# STlink_V3E_Module.net
KiCad netlist of a schematic drawn in Altium Designer
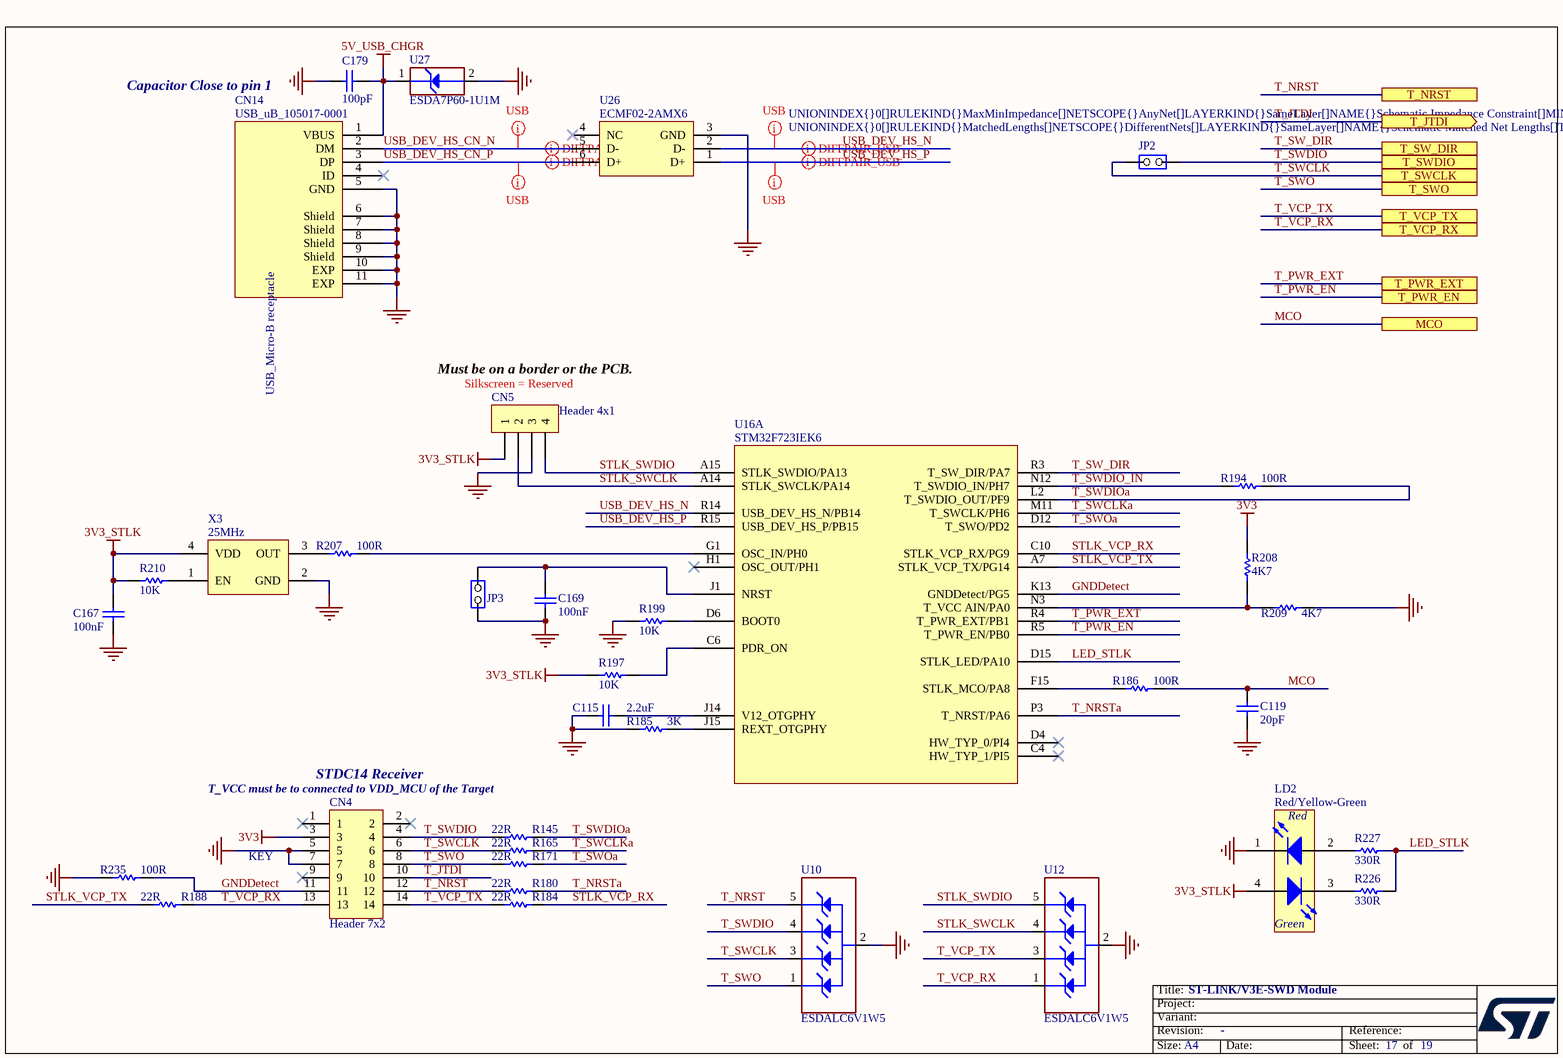
[diagram p0: STlink_V3E_Module.SchDoc]

(export (version "E")
  (design (tool "Eeschema 10.0.6"))
  (components
    (comp (ref "C115")
      (value "2.2uF")
      (footprint "C0603")
      (description "Capacitor, MLCC, 2.2uF, 10V, X5R, 10%, 0603, T=0,8mm")
      (fields
        (field (name "INTERNAL_PART_NUMBER") "MCD-00012")
        (field (name "MANUFACTURER_PART_NUMBER") "CC0603KRX5R6BB225")
        (field (name "PROVIDED_BY") "Subcon")
      )
      (libsource (lib "MCD_PARTS_database") (part "Capacitor"))
    )
    (comp (ref "C119")
      (value "20pF")
      (footprint "C0402")
      (description "Capacitor, MLCC, 20pF, 50V, NPO, 5%, 0402, T=0,5mm")
      (fields
        (field (name "INTERNAL_PART_NUMBER") "MCD-00016")
        (field (name "MANUFACTURER_PART_NUMBER") "CC0402JRNPO9BN200")
        (field (name "PROVIDED_BY") "Subcon")
      )
      (libsource (lib "MCD_PARTS_database") (part "Capacitor"))
    )
    (comp (ref "C167")
      (value "100nF")
      (footprint "C0402")
      (description "Capacitor, MLCC, 100nF, 16V, X7R, +/-10%, 0402, T=0.5mm")
      (fields
        (field (name "INTERNAL_PART_NUMBER") "MCD-00006")
        (field (name "MANUFACTURER_PART_NUMBER") "CC0402KRX7R7BB104")
      )
      (libsource (lib "MCD_PARTS_database") (part "Capacitor"))
    )
    (comp (ref "C169")
      (value "100nF")
      (footprint "C0402")
      (description "Capacitor, MLCC, 100nF, 16V, X7R, +/-10%, 0402, T=0.5mm")
      (fields
        (field (name "INTERNAL_PART_NUMBER") "MCD-00006")
        (field (name "MANUFACTURER_PART_NUMBER") "CC0402KRX7R7BB104")
      )
      (libsource (lib "MCD_PARTS_database") (part "Capacitor"))
    )
    (comp (ref "C179")
      (value "100pF")
      (footprint "C0402")
      (description "Capacitor, MLCC, 100pF, 50V, NPO, 5%, 0402, T=0,5mm")
      (fields
        (field (name "INTERNAL_PART_NUMBER") "MCD-00205")
        (field (name "MANUFACTURER_PART_NUMBER") "CC0402JRNPO9BN101")
        (field (name "PROVIDED_BY") "Subcon")
      )
      (libsource (lib "MCD_PARTS_database") (part "Capacitor"))
    )
    (comp (ref "CN4")
      (value "Header 7x2")
      (footprint "CON_STDC14_Receiver_MEDIUM")
      (description "Header, 7x2, 1.27mm, VR, SMD, T=5.97mm")
      (fields
        (field (name "INTERNAL_PART_NUMBER") "MCD-00592")
        (field (name "MANUFACTURER_PART_NUMBER") "FTSH-107-01-L-DV-K")
      )
      (libsource (lib "MCD_PARTS_database") (part "Header 7x2"))
    )
    (comp (ref "CN5")
      (value "Header 4x1")
      (footprint "CON_SAMTEC_TSW-104-07-G-S")
      (description "Header, 4x1, 2,54mm, VR, TH, Height 5.84mm/2.54mm")
      (fields
        (field (name "INTERNAL_PART_NUMBER") "MCD-00029")
        (field (name "MANUFACTURER_PART_NUMBER") "TSW-104-07-G-S")
        (field (name "PROVIDED_BY") "Subcon")
      )
      (libsource (lib "MCD_PARTS_database") (part "Header 4x1"))
    )
    (comp (ref "CN14")
      (value "USB_uB_105017-0001")
      (footprint "CON_USBMICROB_MOLEX_105017-0001_H2P90")
      (description "USB-MICRO-B, 0.65mm, RA, SMT, Bottom Mount,")
      (fields
        (field (name "INTERNAL_PART_NUMBER") "MCD-00028")
        (field (name "MANUFACTURER_PART_NUMBER") "1050170001")
        (field (name "PROVIDED_BY") "Subcon")
      )
      (libsource (lib "MCD_PARTS_database") (part "USB_uB_105017.0001"))
    )
    (comp (ref "JP2")
      (value "Jumper Header 2x1")
      (footprint "CON_SAMTEC_TSW-102-07-G-S")
      (description "Header, 2x1, 2,54mm, VR, TH, Height 5.84mm/2.54mm")
      (fields
        (field (name "INTERNAL_PART_NUMBER") "MCD-00045")
        (field (name "MANUFACTURER_PART_NUMBER") "TSW-102-07-G-S")
        (field (name "PROVIDED_BY") "Subcon")
      )
      (libsource (lib "MCD_PARTS_database") (part "Jumper Header 2x1"))
    )
    (comp (ref "JP3")
      (value "Jumper Header 2x1")
      (footprint "CON_SAMTEC_TSW-102-07-G-S")
      (description "Header, 2x1, 2,54mm, VR, TH, Height 5.84mm/2.54mm")
      (fields
        (field (name "INTERNAL_PART_NUMBER") "MCD-00045")
        (field (name "MANUFACTURER_PART_NUMBER") "TSW-102-07-G-S")
        (field (name "PROVIDED_BY") "Subcon")
      )
      (libsource (lib "MCD_PARTS_database") (part "Jumper Header 2x1"))
    )
    (comp (ref "LD2")
      (value "Red/Yellow-Green")
      (footprint "LED_BI-GR_HSMF-A201-A00J1")
      (description "LED Bicolor, Red/Yellow-Green , 2V, 20mA, 4-PLCC")
      (fields
        (field (name "INTERNAL_PART_NUMBER") "MCD-02402")
        (field (name "MANUFACTURER_PART_NUMBER") "67-22SURSYGC/S530-A2/TR8")
      )
      (libsource (lib "MCD_PARTS_database") (part "LD_BICOLOR_CMS"))
    )
    (comp (ref "R145")
      (value "22R")
      (footprint "R0402")
      (description "Resistor,22R,0402,1%,1/16W")
      (fields
        (field (name "INTERNAL_PART_NUMBER") "MCD-00189")
        (field (name "MANUFACTURER_PART_NUMBER") "RC0402FR-0722RL")
        (field (name "PROVIDED_BY") "Subcon")
      )
      (libsource (lib "MCD_PARTS_database") (part "Resistor"))
    )
    (comp (ref "R165")
      (value "22R")
      (footprint "R0402")
      (description "Resistor,22R,0402,1%,1/16W")
      (fields
        (field (name "INTERNAL_PART_NUMBER") "MCD-00189")
        (field (name "MANUFACTURER_PART_NUMBER") "RC0402FR-0722RL")
        (field (name "PROVIDED_BY") "Subcon")
      )
      (libsource (lib "MCD_PARTS_database") (part "Resistor"))
    )
    (comp (ref "R171")
      (value "22R")
      (footprint "R0402")
      (description "Resistor,22R,0402,1%,1/16W")
      (fields
        (field (name "INTERNAL_PART_NUMBER") "MCD-00189")
        (field (name "MANUFACTURER_PART_NUMBER") "RC0402FR-0722RL")
        (field (name "PROVIDED_BY") "Subcon")
      )
      (libsource (lib "MCD_PARTS_database") (part "Resistor"))
    )
    (comp (ref "R180")
      (value "22R")
      (footprint "R0402")
      (description "Resistor,22R,0402,1%,1/16W")
      (fields
        (field (name "INTERNAL_PART_NUMBER") "MCD-00189")
        (field (name "MANUFACTURER_PART_NUMBER") "RC0402FR-0722RL")
        (field (name "PROVIDED_BY") "Subcon")
      )
      (libsource (lib "MCD_PARTS_database") (part "Resistor"))
    )
    (comp (ref "R184")
      (value "22R")
      (footprint "R0402")
      (description "Resistor,22R,0402,1%,1/16W")
      (fields
        (field (name "INTERNAL_PART_NUMBER") "MCD-00189")
        (field (name "MANUFACTURER_PART_NUMBER") "RC0402FR-0722RL")
        (field (name "PROVIDED_BY") "Subcon")
      )
      (libsource (lib "MCD_PARTS_database") (part "Resistor"))
    )
    (comp (ref "R185")
      (value "3K")
      (footprint "R0402")
      (description "Resistor,3K,0402,1%,1/16W")
      (fields
        (field (name "INTERNAL_PART_NUMBER") "MCD-00185")
        (field (name "MANUFACTURER_PART_NUMBER") "RC0402FR-073KL")
        (field (name "PROVIDED_BY") "Subcon")
      )
      (libsource (lib "MCD_PARTS_database") (part "Resistor"))
    )
    (comp (ref "R186")
      (value "100R")
      (footprint "R0402")
      (description "Resistor, 100R, 0402, +/- 1%, 1/16W")
      (fields
        (field (name "INTERNAL_PART_NUMBER") "MCD-00067")
        (field (name "MANUFACTURER_PART_NUMBER") "RC0402FR-07100RL")
      )
      (libsource (lib "MCD_PARTS_database") (part "Resistor"))
    )
    (comp (ref "R188")
      (value "22R")
      (footprint "R0402")
      (description "Resistor,22R,0402,1%,1/16W")
      (fields
        (field (name "INTERNAL_PART_NUMBER") "MCD-00189")
        (field (name "MANUFACTURER_PART_NUMBER") "RC0402FR-0722RL")
        (field (name "PROVIDED_BY") "Subcon")
      )
      (libsource (lib "MCD_PARTS_database") (part "Resistor"))
    )
    (comp (ref "R194")
      (value "100R")
      (footprint "R0402")
      (description "Resistor, 100R, 0402, +/- 1%, 1/16W")
      (fields
        (field (name "INTERNAL_PART_NUMBER") "MCD-00067")
        (field (name "MANUFACTURER_PART_NUMBER") "RC0402FR-07100RL")
      )
      (libsource (lib "MCD_PARTS_database") (part "Resistor"))
    )
    (comp (ref "R197")
      (value "10K")
      (footprint "R0402")
      (description "Resistor,10K,0402,1%,1/16W")
      (fields
        (field (name "INTERNAL_PART_NUMBER") "MCD-00053")
        (field (name "MANUFACTURER_PART_NUMBER") "RC0402FR-0710KL")
        (field (name "PROVIDED_BY") "subcon")
      )
      (libsource (lib "MCD_PARTS_database") (part "Resistor"))
    )
    (comp (ref "R199")
      (value "10K")
      (footprint "R0402")
      (description "Resistor,10K,0402,1%,1/16W")
      (fields
        (field (name "INTERNAL_PART_NUMBER") "MCD-00053")
        (field (name "MANUFACTURER_PART_NUMBER") "RC0402FR-0710KL")
        (field (name "PROVIDED_BY") "subcon")
      )
      (libsource (lib "MCD_PARTS_database") (part "Resistor"))
    )
    (comp (ref "R207")
      (value "100R")
      (footprint "R0402")
      (description "Resistor, 100R, 0402, +/- 1%, 1/16W")
      (fields
        (field (name "INTERNAL_PART_NUMBER") "MCD-00067")
        (field (name "MANUFACTURER_PART_NUMBER") "RC0402FR-07100RL")
      )
      (libsource (lib "MCD_PARTS_database") (part "Resistor"))
    )
    (comp (ref "R208")
      (value "4K7")
      (footprint "R0402")
      (description "Resistor,4K7,0402,1%,1/16W")
      (fields
        (field (name "INTERNAL_PART_NUMBER") "MCD-00065")
        (field (name "MANUFACTURER_PART_NUMBER") "RC0402FR-074K7L")
        (field (name "PROVIDED_BY") "Subcon")
      )
      (libsource (lib "MCD_PARTS_database") (part "Resistor"))
    )
    (comp (ref "R209")
      (value "4K7")
      (footprint "R0402")
      (description "Resistor,4K7,0402,1%,1/16W")
      (fields
        (field (name "INTERNAL_PART_NUMBER") "MCD-00065")
        (field (name "MANUFACTURER_PART_NUMBER") "RC0402FR-074K7L")
        (field (name "PROVIDED_BY") "Subcon")
      )
      (libsource (lib "MCD_PARTS_database") (part "Resistor"))
    )
    (comp (ref "R210")
      (value "10K")
      (footprint "R0402")
      (description "Resistor,10K,0402,1%,1/16W")
      (fields
        (field (name "INTERNAL_PART_NUMBER") "MCD-00053")
        (field (name "MANUFACTURER_PART_NUMBER") "RC0402FR-0710KL")
        (field (name "PROVIDED_BY") "subcon")
      )
      (libsource (lib "MCD_PARTS_database") (part "Resistor"))
    )
    (comp (ref "R226")
      (value "330R")
      (footprint "R0603")
      (description "Resistor,330R,0603,1%,1/10W")
      (fields
        (field (name "INTERNAL_PART_NUMBER") "MCD-00197")
        (field (name "MANUFACTURER_PART_NUMBER") "RC0603FR-07330RL")
        (field (name "PROVIDED_BY") "Subcon")
      )
      (libsource (lib "MCD_PARTS_database") (part "Resistor"))
    )
    (comp (ref "R227")
      (value "330R")
      (footprint "R0603")
      (description "Resistor,330R,0603,1%,1/10W")
      (fields
        (field (name "INTERNAL_PART_NUMBER") "MCD-00197")
        (field (name "MANUFACTURER_PART_NUMBER") "RC0603FR-07330RL")
        (field (name "PROVIDED_BY") "Subcon")
      )
      (libsource (lib "MCD_PARTS_database") (part "Resistor"))
    )
    (comp (ref "R235")
      (value "100R")
      (footprint "R0402")
      (description "Resistor, 100R, 0402, +/- 1%, 1/16W")
      (fields
        (field (name "INTERNAL_PART_NUMBER") "MCD-00067")
        (field (name "MANUFACTURER_PART_NUMBER") "RC0402FR-07100RL")
      )
      (libsource (lib "MCD_PARTS_database") (part "Resistor"))
    )
    (comp (ref "U10")
      (value "ESDALC6V1W5")
      (footprint "ESD_SOT323-5L")
      (description "Dual Transil array for ESD protection")
      (fields
        (field (name "INTERNAL_PART_NUMBER") "MCD-00136")
        (field (name "MANUFACTURER") "STMICROELECTRONICS")
        (field (name "PROVIDED_BY") "Subcon")
      )
      (libsource (lib "MCD_PARTS_database") (part "ESDALC6V1W5"))
    )
    (comp (ref "U12")
      (value "ESDALC6V1W5")
      (footprint "ESD_SOT323-5L")
      (description "Dual Transil array for ESD protection")
      (fields
        (field (name "INTERNAL_PART_NUMBER") "MCD-00136")
        (field (name "MANUFACTURER") "STMICROELECTRONICS")
        (field (name "PROVIDED_BY") "Subcon")
      )
      (libsource (lib "MCD_PARTS_database") (part "ESDALC6V1W5"))
    )
    (comp (ref "U16")
      (value "STM32F723IEK6")
      (footprint "ICC_UFBGA201_176+25_10X10_P065")
      (description "STM32F723IEK  (STM32F7) BGA176")
      (fields
        (field (name "INTERNAL_PART_NUMBER") "MCD-00596")
        (field (name "MANUFACTURER") "STMICROELECTRONICS")
        (field (name "PROVIDED_BY") "SUBCO with ST control")
      )
      (libsource (lib "MCD_PARTS_database") (part "ST-LINKV3E_SWD"))
    )
    (comp (ref "U26")
      (value "ECMF02-2AMX6")
      (footprint "ESD_QFN-6L_1P7X1P5_P050")
      (description "Common mode filter with ESD protection for USB 2.0 interface")
      (fields
        (field (name "INTERNAL_PART_NUMBER") "MCD-00649")
        (field (name "MANUFACTURER") "STMICROELECTRONICS")
        (field (name "PROVIDED_BY") "Subcon")
      )
      (libsource (lib "MCD_PARTS_database") (part "ECMF02-2AMX6"))
    )
    (comp (ref "U27")
      (value "ESDA7P60-1U1M")
      (footprint "ESD_QFN2_1P6X1_P125")
      (description "High power transient voltage suppressor, 7V breakdown")
      (fields
        (field (name "INTERNAL_PART_NUMBER") "MCD-00251")
        (field (name "MANUFACTURER") "STMICROELECTRONICS")
        (field (name "PROVIDED_BY") "Subcon")
      )
      (libsource (lib "MCD_PARTS_database") (part "ESDA7P60-1U1M"))
    )
    (comp (ref "X3")
      (value "25MHz")
      (footprint "OSC_NDK_NZ2520SB_4P")
      (description "Oscillator 25.00Mhz, -+50PPM, 3.3V, Temp -55 to +125°C")
      (fields
        (field (name "INTERNAL_PART_NUMBER") "MCD-00597")
        (field (name "MANUFACTURER_PART_NUMBER") "NZ2520SH-25MHZ-END4869C")
        (field (name "PROVIDED_BY") "STM")
      )
      (libsource (lib "MCD_PARTS_database") (part "Oscillator_4pins"))
    )
  )
  (nets
    (net (code "1") (name "/GNDDetect") (class "Default")
      (node (ref "CN4") (pin "11") (pinfunction "11_11") (pintype "passive"))
      (node (ref "R235") (pin "2") (pinfunction "2_2") (pintype "passive"))
      (node (ref "U16") (pin "K13") (pinfunction "GNDDetect/PG5_K13") (pintype "passive"))
    )
    (net (code "2") (name "/LED_STLK") (class "Default")
      (node (ref "R226") (pin "2") (pinfunction "2_2") (pintype "passive"))
      (node (ref "R227") (pin "2") (pinfunction "2_2") (pintype "passive"))
      (node (ref "U16") (pin "D15") (pinfunction "STLK_LED/PA10_D15") (pintype "passive"))
    )
    (net (code "3") (name "/MCO") (class "Default")
      (node (ref "C119") (pin "2") (pinfunction "2_2") (pintype "passive"))
      (node (ref "R186") (pin "2") (pinfunction "2_2") (pintype "passive"))
    )
    (net (code "4") (name "/STLK_SWCLK") (class "Default")
      (node (ref "CN5") (pin "2") (pinfunction "2_2") (pintype "passive"))
      (node (ref "U12") (pin "4") (pinfunction "IO3_4") (pintype "passive"))
      (node (ref "U16") (pin "A14") (pinfunction "STLK_SWCLK/PA14_A14") (pintype "passive"))
    )
    (net (code "5") (name "/STLK_SWDIO") (class "Default")
      (node (ref "CN5") (pin "4") (pinfunction "4_4") (pintype "passive"))
      (node (ref "U12") (pin "5") (pinfunction "IO4_5") (pintype "passive"))
      (node (ref "U16") (pin "A15") (pinfunction "STLK_SWDIO/PA13_A15") (pintype "passive"))
    )
    (net (code "6") (name "/STLK_VCP_RX") (class "Default")
      (node (ref "R184") (pin "2") (pinfunction "2_2") (pintype "passive"))
      (node (ref "U16") (pin "C10") (pinfunction "STLK_VCP_RX/PG9_C10") (pintype "passive"))
    )
    (net (code "7") (name "/STLK_VCP_TX") (class "Default")
      (node (ref "R188") (pin "1") (pinfunction "1_1") (pintype "passive"))
      (node (ref "U16") (pin "A7") (pinfunction "STLK_VCP_TX/PG14_A7") (pintype "passive"))
    )
    (net (code "8") (name "/T_JTDI") (class "Default")
      (node (ref "CN4") (pin "10") (pinfunction "10_10") (pintype "passive"))
    )
    (net (code "9") (name "/T_NRST") (class "Default")
      (node (ref "CN4") (pin "12") (pinfunction "12_12") (pintype "passive"))
      (node (ref "R180") (pin "1") (pinfunction "1_1") (pintype "passive"))
      (node (ref "U10") (pin "5") (pinfunction "IO4_5") (pintype "passive"))
    )
    (net (code "10") (name "/T_NRSTa") (class "Default")
      (node (ref "R180") (pin "2") (pinfunction "2_2") (pintype "passive"))
      (node (ref "U16") (pin "P3") (pinfunction "T_NRST/PA6_P3") (pintype "passive"))
    )
    (net (code "11") (name "/T_PWR_EN") (class "Default")
      (node (ref "U16") (pin "R5") (pinfunction "T_PWR_EN/PB0_R5") (pintype "passive"))
    )
    (net (code "12") (name "/T_PWR_EXT") (class "Default")
      (node (ref "U16") (pin "R4") (pinfunction "T_PWR_EXT/PB1_R4") (pintype "passive"))
    )
    (net (code "13") (name "/T_SWCLK") (class "Default")
      (node (ref "CN4") (pin "6") (pinfunction "6_6") (pintype "passive"))
      (node (ref "JP2") (pin "1") (pinfunction "COMMON_1") (pintype "passive"))
      (node (ref "R165") (pin "1") (pinfunction "1_1") (pintype "passive"))
      (node (ref "U10") (pin "3") (pinfunction "IO2_3") (pintype "passive"))
    )
    (net (code "14") (name "/T_SWCLKa") (class "Default")
      (node (ref "R165") (pin "2") (pinfunction "2_2") (pintype "passive"))
      (node (ref "U16") (pin "M11") (pinfunction "T_SWCLK/PH6_M11") (pintype "passive"))
    )
    (net (code "15") (name "/T_SWDIO") (class "Default")
      (node (ref "CN4") (pin "4") (pinfunction "4_4") (pintype "passive"))
      (node (ref "JP2") (pin "2") (pinfunction "NO_2") (pintype "passive"))
      (node (ref "R145") (pin "1") (pinfunction "1_1") (pintype "passive"))
      (node (ref "U10") (pin "4") (pinfunction "IO3_4") (pintype "passive"))
    )
    (net (code "16") (name "/T_SWDIO_IN") (class "Default")
      (node (ref "R194") (pin "1") (pinfunction "1_1") (pintype "passive"))
      (node (ref "U16") (pin "N12") (pinfunction "T_SWDIO_IN/PH7_N12") (pintype "passive"))
    )
    (net (code "17") (name "/T_SWDIOa") (class "Default")
      (node (ref "R145") (pin "2") (pinfunction "2_2") (pintype "passive"))
      (node (ref "R194") (pin "2") (pinfunction "2_2") (pintype "passive"))
      (node (ref "U16") (pin "L2") (pinfunction "T_SWDIO_OUT/PF9_L2") (pintype "passive"))
    )
    (net (code "18") (name "/T_SWO") (class "Default")
      (node (ref "CN4") (pin "8") (pinfunction "8_8") (pintype "passive"))
      (node (ref "R171") (pin "1") (pinfunction "1_1") (pintype "passive"))
      (node (ref "U10") (pin "1") (pinfunction "IO1_1") (pintype "passive"))
    )
    (net (code "19") (name "/T_SWOa") (class "Default")
      (node (ref "R171") (pin "2") (pinfunction "2_2") (pintype "passive"))
      (node (ref "U16") (pin "D12") (pinfunction "T_SWO/PD2_D12") (pintype "passive"))
    )
    (net (code "20") (name "/T_SW_DIR") (class "Default")
      (node (ref "U16") (pin "R3") (pinfunction "T_SW_DIR/PA7_R3") (pintype "passive"))
    )
    (net (code "21") (name "/T_VCP_RX") (class "Default")
      (node (ref "CN4") (pin "13") (pinfunction "13_13") (pintype "passive"))
      (node (ref "R188") (pin "2") (pinfunction "2_2") (pintype "passive"))
      (node (ref "U12") (pin "1") (pinfunction "IO1_1") (pintype "passive"))
    )
    (net (code "22") (name "/T_VCP_TX") (class "Default")
      (node (ref "CN4") (pin "14") (pinfunction "14_14") (pintype "passive"))
      (node (ref "R184") (pin "1") (pinfunction "1_1") (pintype "passive"))
      (node (ref "U12") (pin "3") (pinfunction "IO2_3") (pintype "passive"))
    )
    (net (code "23") (name "/USB_DEV_HS_CN_N") (class "Default")
      (node (ref "CN14") (pin "2") (pinfunction "DM_2") (pintype "passive"))
      (node (ref "U26") (pin "5") (pinfunction "D-_5") (pintype "passive"))
    )
    (net (code "24") (name "/USB_DEV_HS_CN_P") (class "Default")
      (node (ref "CN14") (pin "3") (pinfunction "DP_3") (pintype "passive"))
      (node (ref "U26") (pin "6") (pinfunction "D+_6") (pintype "passive"))
    )
    (net (code "25") (name "/USB_DEV_HS_N") (class "Default")
      (node (ref "U16") (pin "R14") (pinfunction "USB_DEV_HS_N/PB14_R14") (pintype "passive"))
      (node (ref "U26") (pin "2") (pinfunction "D-_2") (pintype "passive"))
    )
    (net (code "26") (name "/USB_DEV_HS_P") (class "Default")
      (node (ref "U16") (pin "R15") (pinfunction "USB_DEV_HS_P/PB15_R15") (pintype "passive"))
      (node (ref "U26") (pin "1") (pinfunction "D+_1") (pintype "passive"))
    )
    (net (code "27") (name "3V3") (class "Default")
      (node (ref "CN4") (pin "3") (pinfunction "3_3") (pintype "passive"))
      (node (ref "R208") (pin "2") (pinfunction "2_2") (pintype "passive"))
    )
    (net (code "28") (name "3V3_STLK") (class "Default")
      (node (ref "C167") (pin "2") (pinfunction "2_2") (pintype "passive"))
      (node (ref "CN5") (pin "1") (pinfunction "1_1") (pintype "passive"))
      (node (ref "LD2") (pin "4") (pinfunction "YellowGreen_anode_4") (pintype "passive"))
      (node (ref "R197") (pin "1") (pinfunction "1_1") (pintype "passive"))
      (node (ref "R210") (pin "1") (pinfunction "1_1") (pintype "passive"))
      (node (ref "X3") (pin "4") (pinfunction "VDD_4") (pintype "passive"))
    )
    (net (code "29") (name "5V_USB_CHGR") (class "Default")
      (node (ref "C179") (pin "2") (pinfunction "2_2") (pintype "passive"))
      (node (ref "CN14") (pin "1") (pinfunction "VBUS_1") (pintype "passive"))
      (node (ref "U27") (pin "1") (pinfunction "IO1_1") (pintype "passive"))
    )
    (net (code "30") (name "GND") (class "Default")
      (node (ref "C115") (pin "1") (pinfunction "1_1") (pintype "passive"))
      (node (ref "C119") (pin "1") (pinfunction "1_1") (pintype "passive"))
      (node (ref "C167") (pin "1") (pinfunction "1_1") (pintype "passive"))
      (node (ref "C169") (pin "1") (pinfunction "1_1") (pintype "passive"))
      (node (ref "C179") (pin "1") (pinfunction "1_1") (pintype "passive"))
      (node (ref "CN14") (pin "10") (pinfunction "EXP_10") (pintype "passive"))
      (node (ref "CN14") (pin "11") (pinfunction "EXP_11") (pintype "passive"))
      (node (ref "CN14") (pin "5") (pinfunction "GND_5") (pintype "passive"))
      (node (ref "CN14") (pin "6") (pinfunction "Shield_6") (pintype "passive"))
      (node (ref "CN14") (pin "7") (pinfunction "Shield_7") (pintype "passive"))
      (node (ref "CN14") (pin "8") (pinfunction "Shield_8") (pintype "passive"))
      (node (ref "CN14") (pin "9") (pinfunction "Shield_9") (pintype "passive"))
      (node (ref "CN4") (pin "5") (pinfunction "5_5") (pintype "passive"))
      (node (ref "CN4") (pin "7") (pinfunction "7_7") (pintype "passive"))
      (node (ref "CN5") (pin "3") (pinfunction "3_3") (pintype "passive"))
      (node (ref "JP3") (pin "1") (pinfunction "COMMON_1") (pintype "passive"))
      (node (ref "LD2") (pin "1") (pinfunction "RED_cathode_1") (pintype "passive"))
      (node (ref "R185") (pin "1") (pinfunction "1_1") (pintype "passive"))
      (node (ref "R199") (pin "1") (pinfunction "1_1") (pintype "passive"))
      (node (ref "R209") (pin "2") (pinfunction "2_2") (pintype "passive"))
      (node (ref "R235") (pin "1") (pinfunction "1_1") (pintype "passive"))
      (node (ref "U10") (pin "2") (pinfunction "GND_2") (pintype "passive"))
      (node (ref "U12") (pin "2") (pinfunction "GND_2") (pintype "passive"))
      (node (ref "U26") (pin "3") (pinfunction "GND_3") (pintype "passive"))
      (node (ref "U27") (pin "2") (pinfunction "GND_2") (pintype "passive"))
      (node (ref "X3") (pin "2") (pinfunction "GND_2") (pintype "passive"))
    )
    (net (code "31") (name "Net-(JP3-NO)") (class "Default")
      (node (ref "C169") (pin "2") (pinfunction "2_2") (pintype "passive"))
      (node (ref "JP3") (pin "2") (pinfunction "NO_2") (pintype "passive"))
      (node (ref "U16") (pin "J1") (pinfunction "NRST_J1") (pintype "passive"))
    )
    (net (code "32") (name "Net-(LD2-Red_anode)") (class "Default")
      (node (ref "LD2") (pin "2") (pinfunction "Red_anode_2") (pintype "passive"))
      (node (ref "R227") (pin "1") (pinfunction "1_1") (pintype "passive"))
    )
    (net (code "33") (name "Net-(LD2-YellowGreen_cathode)") (class "Default")
      (node (ref "LD2") (pin "3") (pinfunction "YellowGreen_cathode_3") (pintype "passive"))
      (node (ref "R226") (pin "1") (pinfunction "1_1") (pintype "passive"))
    )
    (net (code "34") (name "Net-(U16A-BOOT0)") (class "Default")
      (node (ref "R199") (pin "2") (pinfunction "2_2") (pintype "passive"))
      (node (ref "U16") (pin "D6") (pinfunction "BOOT0_D6") (pintype "passive"))
    )
    (net (code "35") (name "Net-(U16A-OSC_IN{slash}PH0)") (class "Default")
      (node (ref "R207") (pin "2") (pinfunction "2_2") (pintype "passive"))
      (node (ref "U16") (pin "G1") (pinfunction "OSC_IN/PH0_G1") (pintype "passive"))
    )
    (net (code "36") (name "Net-(U16A-PDR_ON)") (class "Default")
      (node (ref "R197") (pin "2") (pinfunction "2_2") (pintype "passive"))
      (node (ref "U16") (pin "C6") (pinfunction "PDR_ON_C6") (pintype "passive"))
    )
    (net (code "37") (name "Net-(U16A-REXT_OTGPHY)") (class "Default")
      (node (ref "R185") (pin "2") (pinfunction "2_2") (pintype "passive"))
      (node (ref "U16") (pin "J15") (pinfunction "REXT_OTGPHY_J15") (pintype "passive"))
    )
    (net (code "38") (name "Net-(U16A-STLK_MCO{slash}PA8)") (class "Default")
      (node (ref "R186") (pin "1") (pinfunction "1_1") (pintype "passive"))
      (node (ref "U16") (pin "F15") (pinfunction "STLK_MCO/PA8_F15") (pintype "passive"))
    )
    (net (code "39") (name "Net-(U16A-T_VCC_AIN{slash}PA0)") (class "Default")
      (node (ref "R208") (pin "1") (pinfunction "1_1") (pintype "passive"))
      (node (ref "R209") (pin "1") (pinfunction "1_1") (pintype "passive"))
      (node (ref "U16") (pin "N3") (pinfunction "T_VCC_AIN/PA0_N3") (pintype "passive"))
    )
    (net (code "40") (name "Net-(U16A-V12_OTGPHY)") (class "Default")
      (node (ref "C115") (pin "2") (pinfunction "2_2") (pintype "passive"))
      (node (ref "U16") (pin "J14") (pinfunction "V12_OTGPHY_J14") (pintype "passive"))
    )
    (net (code "41") (name "Net-(X3-EN)") (class "Default")
      (node (ref "R210") (pin "2") (pinfunction "2_2") (pintype "passive"))
      (node (ref "X3") (pin "1") (pinfunction "EN_1") (pintype "passive"))
    )
    (net (code "42") (name "Net-(X3-OUT)") (class "Default")
      (node (ref "R207") (pin "1") (pinfunction "1_1") (pintype "passive"))
      (node (ref "X3") (pin "3") (pinfunction "OUT_3") (pintype "passive"))
    )
    (net (code "43") (name "unconnected-(CN4-Pad1)") (class "Default")
      (node (ref "CN4") (pin "1") (pinfunction "1_1") (pintype "passive+no_connect"))
    )
    (net (code "44") (name "unconnected-(CN4-Pad2)") (class "Default")
      (node (ref "CN4") (pin "2") (pinfunction "2_2") (pintype "passive+no_connect"))
    )
    (net (code "45") (name "unconnected-(CN4-Pad9)") (class "Default")
      (node (ref "CN4") (pin "9") (pinfunction "9_9") (pintype "passive+no_connect"))
    )
    (net (code "46") (name "unconnected-(CN14-ID-Pad4)") (class "Default")
      (node (ref "CN14") (pin "4") (pinfunction "ID_4") (pintype "passive+no_connect"))
    )
    (net (code "47") (name "unconnected-(U16A-HW_TYP_0{slash}PI4-PadD4)") (class "Default")
      (node (ref "U16") (pin "D4") (pinfunction "HW_TYP_0/PI4_D4") (pintype "passive+no_connect"))
    )
    (net (code "48") (name "unconnected-(U16A-HW_TYP_1{slash}PI5-PadC4)") (class "Default")
      (node (ref "U16") (pin "C4") (pinfunction "HW_TYP_1/PI5_C4") (pintype "passive+no_connect"))
    )
    (net (code "49") (name "unconnected-(U16A-OSC_OUT{slash}PH1-PadH1)") (class "Default")
      (node (ref "U16") (pin "H1") (pinfunction "OSC_OUT/PH1_H1") (pintype "passive+no_connect"))
    )
    (net (code "50") (name "unconnected-(U26-NC-Pad4)") (class "Default")
      (node (ref "U26") (pin "4") (pinfunction "NC_4") (pintype "passive+no_connect"))
    )
  )
)
